# Sheet2.net
KiCad netlist of a schematic drawn in Altium Designer
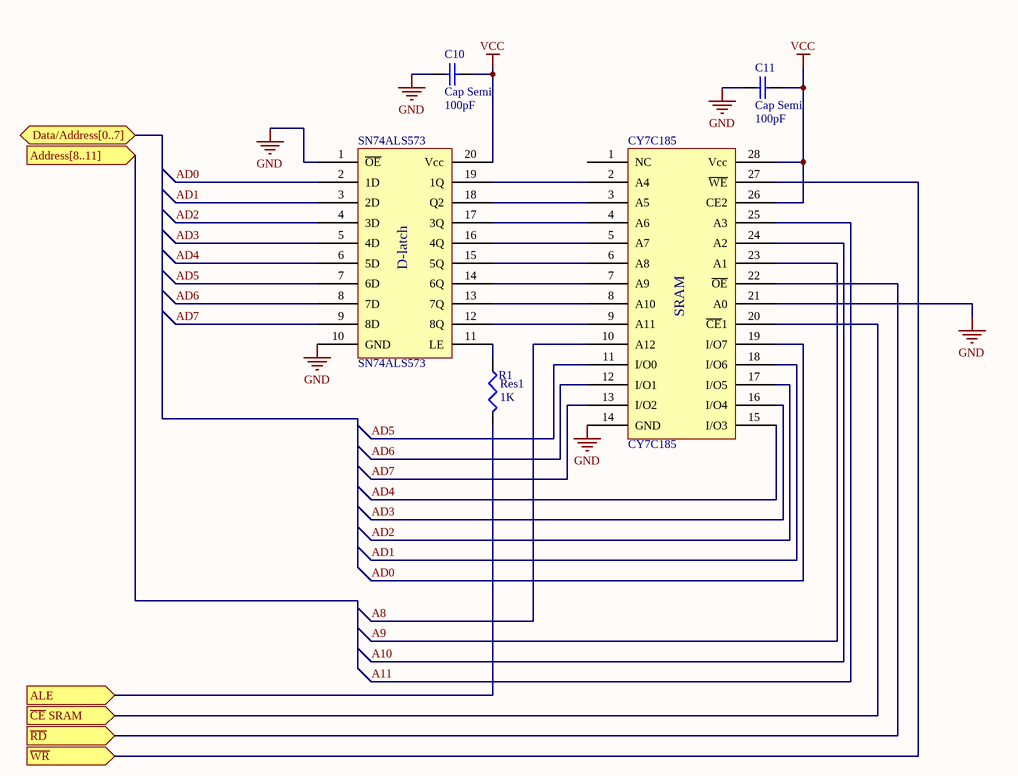
[diagram p0: Sheet2.SchDoc]

(export (version "E")
  (design (tool "Eeschema 10.0.6"))
  (components
    (comp (ref "C10")
      (value "Cap Semi")
      (footprint "C1210")
      (description "Capacitor (Semiconductor SIM Model)")
      (fields (field (name "ALTIUM_VALUE") "100pF") (field (name "PUBLISHER") "Altium Limited"))
      (libsource (lib "Miscellaneous Devices") (part "Cap Semi"))
    )
    (comp (ref "C11")
      (value "Cap Semi")
      (footprint "C1210")
      (description "Capacitor (Semiconductor SIM Model)")
      (fields (field (name "ALTIUM_VALUE") "100pF") (field (name "PUBLISHER") "Altium Limited"))
      (libsource (lib "Miscellaneous Devices") (part "Cap Semi"))
    )
    (comp (ref "CY7C185")
      (value "CY7C185")
      (footprint "CY7C185 SOIC 28-PIN")
      (description "SRAM - Static Random Access Memory")
      (libsource (lib "IIDKLib") (part "CY7C185"))
    )
    (comp (ref "R1")
      (value "Res1")
      (footprint "14-1210")
      (description "Resistor")
      (fields (field (name "ALTIUM_VALUE") "1K") (field (name "PUBLISHER") "Altium Limited"))
      (libsource (lib "Miscellaneous Devices") (part "Res3"))
    )
    (comp (ref "SN74ALS573")
      (value "SN74ALS573")
      (footprint "IIDKLib:D-Latch SOIC 20-PIN")
      (description "D-Latch")
      (libsource (lib "IIDKLib") (part "SN74ALS573"))
    )
  )
  (nets
    (net (code "13") (name "/A8") (class "Default")
      (node (ref "CY7C185") (pin "10") (pinfunction "A12_10") (pintype "passive"))
    )
    (net (code "14") (name "/A9") (class "Default")
      (node (ref "CY7C185") (pin "23") (pinfunction "A1_23") (pintype "passive"))
    )
    (net (code "15") (name "/A10") (class "Default")
      (node (ref "CY7C185") (pin "24") (pinfunction "A2_24") (pintype "passive"))
    )
    (net (code "16") (name "/A11") (class "Default")
      (node (ref "CY7C185") (pin "25") (pinfunction "A3_25") (pintype "passive"))
    )
    (net (code "17") (name "/AD0") (class "Default")
      (node (ref "CY7C185") (pin "19") (pinfunction "I/O7_19") (pintype "passive"))
      (node (ref "SN74ALS573") (pin "2") (pinfunction "1D_2") (pintype "passive"))
    )
    (net (code "18") (name "/AD1") (class "Default")
      (node (ref "CY7C185") (pin "18") (pinfunction "I/O6_18") (pintype "passive"))
      (node (ref "SN74ALS573") (pin "3") (pinfunction "2D_3") (pintype "passive"))
    )
    (net (code "19") (name "/AD2") (class "Default")
      (node (ref "CY7C185") (pin "17") (pinfunction "I/O5_17") (pintype "passive"))
      (node (ref "SN74ALS573") (pin "4") (pinfunction "3D_4") (pintype "passive"))
    )
    (net (code "20") (name "/AD3") (class "Default")
      (node (ref "CY7C185") (pin "16") (pinfunction "I/O4_16") (pintype "passive"))
      (node (ref "SN74ALS573") (pin "5") (pinfunction "4D_5") (pintype "passive"))
    )
    (net (code "21") (name "/AD4") (class "Default")
      (node (ref "CY7C185") (pin "15") (pinfunction "I/O3_15") (pintype "passive"))
      (node (ref "SN74ALS573") (pin "6") (pinfunction "5D_6") (pintype "passive"))
    )
    (net (code "22") (name "/AD5") (class "Default")
      (node (ref "CY7C185") (pin "11") (pinfunction "I/O0_11") (pintype "passive"))
      (node (ref "SN74ALS573") (pin "7") (pinfunction "6D_7") (pintype "passive"))
    )
    (net (code "23") (name "/AD6") (class "Default")
      (node (ref "CY7C185") (pin "12") (pinfunction "I/O1_12") (pintype "passive"))
      (node (ref "SN74ALS573") (pin "8") (pinfunction "7D_8") (pintype "passive"))
    )
    (net (code "24") (name "/AD7") (class "Default")
      (node (ref "CY7C185") (pin "13") (pinfunction "I/O2_13") (pintype "passive"))
      (node (ref "SN74ALS573") (pin "9") (pinfunction "8D_9") (pintype "passive"))
    )
    (net (code "25") (name "/ALE") (class "Default")
      (node (ref "R1") (pin "2") (pinfunction "2_2") (pintype "passive"))
    )
    (net (code "28") (name "/~{CE} SRAM") (class "Default")
      (node (ref "CY7C185") (pin "20") (pinfunction "~{CE}1_20") (pintype "passive"))
    )
    (net (code "29") (name "/~{RD}") (class "Default")
      (node (ref "CY7C185") (pin "22") (pinfunction "~{OE}_22") (pintype "passive"))
    )
    (net (code "30") (name "/~{WR}") (class "Default")
      (node (ref "CY7C185") (pin "27") (pinfunction "~{WE}_27") (pintype "passive"))
    )
    (net (code "31") (name "GND") (class "Default")
      (node (ref "C10") (pin "2") (pinfunction "2_2") (pintype "passive"))
      (node (ref "C11") (pin "2") (pinfunction "2_2") (pintype "passive"))
      (node (ref "CY7C185") (pin "14") (pinfunction "GND_14") (pintype "power_in"))
      (node (ref "CY7C185") (pin "21") (pinfunction "A0_21") (pintype "passive"))
      (node (ref "SN74ALS573") (pin "1") (pinfunction "~{OE}_1") (pintype "passive"))
      (node (ref "SN74ALS573") (pin "10") (pinfunction "GND_10") (pintype "power_in"))
    )
    (net (code "32") (name "Net-(CY7C185-A4)") (class "Default")
      (node (ref "CY7C185") (pin "2") (pinfunction "A4_2") (pintype "passive"))
      (node (ref "SN74ALS573") (pin "19") (pinfunction "1Q_19") (pintype "passive"))
    )
    (net (code "33") (name "Net-(CY7C185-A5)") (class "Default")
      (node (ref "CY7C185") (pin "3") (pinfunction "A5_3") (pintype "passive"))
      (node (ref "SN74ALS573") (pin "18") (pinfunction "Q2_18") (pintype "passive"))
    )
    (net (code "34") (name "Net-(CY7C185-A6)") (class "Default")
      (node (ref "CY7C185") (pin "4") (pinfunction "A6_4") (pintype "passive"))
      (node (ref "SN74ALS573") (pin "17") (pinfunction "3Q_17") (pintype "passive"))
    )
    (net (code "35") (name "Net-(CY7C185-A7)") (class "Default")
      (node (ref "CY7C185") (pin "5") (pinfunction "A7_5") (pintype "passive"))
      (node (ref "SN74ALS573") (pin "16") (pinfunction "4Q_16") (pintype "passive"))
    )
    (net (code "36") (name "Net-(CY7C185-A8)") (class "Default")
      (node (ref "CY7C185") (pin "6") (pinfunction "A8_6") (pintype "passive"))
      (node (ref "SN74ALS573") (pin "15") (pinfunction "5Q_15") (pintype "passive"))
    )
    (net (code "37") (name "Net-(CY7C185-A9)") (class "Default")
      (node (ref "CY7C185") (pin "7") (pinfunction "A9_7") (pintype "passive"))
      (node (ref "SN74ALS573") (pin "14") (pinfunction "6Q_14") (pintype "passive"))
    )
    (net (code "38") (name "Net-(CY7C185-A10)") (class "Default")
      (node (ref "CY7C185") (pin "8") (pinfunction "A10_8") (pintype "passive"))
      (node (ref "SN74ALS573") (pin "13") (pinfunction "7Q_13") (pintype "passive"))
    )
    (net (code "39") (name "Net-(CY7C185-A11)") (class "Default")
      (node (ref "CY7C185") (pin "9") (pinfunction "A11_9") (pintype "passive"))
      (node (ref "SN74ALS573") (pin "12") (pinfunction "8Q_12") (pintype "passive"))
    )
    (net (code "40") (name "Net-(SN74ALS573-LE)") (class "Default")
      (node (ref "R1") (pin "1") (pinfunction "1_1") (pintype "passive"))
      (node (ref "SN74ALS573") (pin "11") (pinfunction "LE_11") (pintype "passive"))
    )
    (net (code "41") (name "VCC") (class "Default")
      (node (ref "C10") (pin "1") (pinfunction "1_1") (pintype "passive"))
      (node (ref "C11") (pin "1") (pinfunction "1_1") (pintype "passive"))
      (node (ref "CY7C185") (pin "26") (pinfunction "CE2_26") (pintype "passive"))
      (node (ref "CY7C185") (pin "28") (pinfunction "Vcc_28") (pintype "power_in"))
      (node (ref "SN74ALS573") (pin "20") (pinfunction "Vcc_20") (pintype "power_in"))
    )
    (net (code "42") (name "unconnected-(CY7C185-NC-Pad1)") (class "Default")
      (node (ref "CY7C185") (pin "1") (pinfunction "NC_1") (pintype "passive"))
    )
  )
)
